# encoder_board.net
KiCad netlist of a schematic drawn in EAGLE
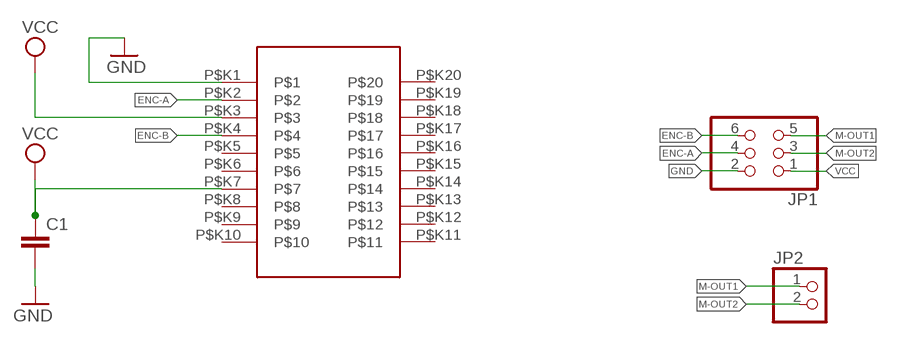
[diagram p0: schematic, sheet 1]

(export (version "E")
  (design (tool "Eeschema 10.0.6"))
  (components
    (comp (ref "C1")
      (value "C-EUC0805K")
      (footprint "eagle-import:C0805K")
      (libsource (lib "eagle-import") (part "C-EUC0805K"))
    )
    (comp (ref "JP1")
      (value "PINHD-2X3")
      (footprint "eagle-import:2X03")
      (libsource (lib "eagle-import") (part "PINHD-2X3"))
    )
    (comp (ref "JP2")
      (value "PINHD-1X2")
      (footprint "eagle-import:1X02")
      (libsource (lib "eagle-import") (part "PINHD-1X2"))
    )
    (comp (ref "U$1")
      (value "TSSOP20")
      (footprint "eagle-import:TSSOP20")
      (libsource (lib "eagle-import") (part "TSSOP20"))
    )
  )
  (nets
    (net (code "1") (name "ENC-A") (class "Default")
      (node (ref "JP1") (pin "4") (pinfunction "4_4") (pintype "passive"))
      (node (ref "U$1") (pin "P$K2") (pinfunction "P$2_P$K2") (pintype "bidirectional"))
    )
    (net (code "2") (name "ENC-B") (class "Default")
      (node (ref "JP1") (pin "6") (pinfunction "6_6") (pintype "passive"))
      (node (ref "U$1") (pin "P$K4") (pinfunction "P$4_P$K4") (pintype "bidirectional"))
    )
    (net (code "3") (name "GND") (class "Default")
      (node (ref "C1") (pin "2") (pinfunction "2_2") (pintype "passive"))
      (node (ref "JP1") (pin "2") (pinfunction "2_2") (pintype "passive"))
      (node (ref "U$1") (pin "P$K1") (pinfunction "P$1_P$K1") (pintype "bidirectional"))
    )
    (net (code "4") (name "M-OUT1") (class "Default")
      (node (ref "JP1") (pin "5") (pinfunction "5_5") (pintype "passive"))
      (node (ref "JP2") (pin "1") (pinfunction "1_1") (pintype "passive"))
    )
    (net (code "5") (name "M-OUT2") (class "Default")
      (node (ref "JP1") (pin "3") (pinfunction "3_3") (pintype "passive"))
      (node (ref "JP2") (pin "2") (pinfunction "2_2") (pintype "passive"))
    )
    (net (code "6") (name "VCC") (class "Default")
      (node (ref "C1") (pin "1") (pinfunction "1_1") (pintype "passive"))
      (node (ref "JP1") (pin "1") (pinfunction "1_1") (pintype "passive"))
      (node (ref "U$1") (pin "P$K3") (pinfunction "P$3_P$K3") (pintype "bidirectional"))
      (node (ref "U$1") (pin "P$K7") (pinfunction "P$7_P$K7") (pintype "bidirectional"))
    )
    (net (code "7") (name "unconnected-(U$1-P$5-PadP$K5)") (class "Default")
      (node (ref "U$1") (pin "P$K5") (pinfunction "P$5_P$K5") (pintype "bidirectional"))
    )
    (net (code "8") (name "unconnected-(U$1-P$6-PadP$K6)") (class "Default")
      (node (ref "U$1") (pin "P$K6") (pinfunction "P$6_P$K6") (pintype "bidirectional"))
    )
    (net (code "9") (name "unconnected-(U$1-P$8-PadP$K8)") (class "Default")
      (node (ref "U$1") (pin "P$K8") (pinfunction "P$8_P$K8") (pintype "bidirectional"))
    )
    (net (code "10") (name "unconnected-(U$1-P$9-PadP$K9)") (class "Default")
      (node (ref "U$1") (pin "P$K9") (pinfunction "P$9_P$K9") (pintype "bidirectional"))
    )
    (net (code "11") (name "unconnected-(U$1-P$10-PadP$K10)") (class "Default")
      (node (ref "U$1") (pin "P$K10") (pinfunction "P$10_P$K10") (pintype "bidirectional"))
    )
    (net (code "12") (name "unconnected-(U$1-P$11-PadP$K11)") (class "Default")
      (node (ref "U$1") (pin "P$K11") (pinfunction "P$11_P$K11") (pintype "bidirectional"))
    )
    (net (code "13") (name "unconnected-(U$1-P$12-PadP$K12)") (class "Default")
      (node (ref "U$1") (pin "P$K12") (pinfunction "P$12_P$K12") (pintype "bidirectional"))
    )
    (net (code "14") (name "unconnected-(U$1-P$13-PadP$K13)") (class "Default")
      (node (ref "U$1") (pin "P$K13") (pinfunction "P$13_P$K13") (pintype "bidirectional"))
    )
    (net (code "15") (name "unconnected-(U$1-P$14-PadP$K14)") (class "Default")
      (node (ref "U$1") (pin "P$K14") (pinfunction "P$14_P$K14") (pintype "bidirectional"))
    )
    (net (code "16") (name "unconnected-(U$1-P$15-PadP$K15)") (class "Default")
      (node (ref "U$1") (pin "P$K15") (pinfunction "P$15_P$K15") (pintype "bidirectional"))
    )
    (net (code "17") (name "unconnected-(U$1-P$16-PadP$K16)") (class "Default")
      (node (ref "U$1") (pin "P$K16") (pinfunction "P$16_P$K16") (pintype "bidirectional"))
    )
    (net (code "18") (name "unconnected-(U$1-P$17-PadP$K17)") (class "Default")
      (node (ref "U$1") (pin "P$K17") (pinfunction "P$17_P$K17") (pintype "bidirectional"))
    )
    (net (code "19") (name "unconnected-(U$1-P$18-PadP$K18)") (class "Default")
      (node (ref "U$1") (pin "P$K18") (pinfunction "P$18_P$K18") (pintype "bidirectional"))
    )
    (net (code "20") (name "unconnected-(U$1-P$19-PadP$K19)") (class "Default")
      (node (ref "U$1") (pin "P$K19") (pinfunction "P$19_P$K19") (pintype "bidirectional"))
    )
    (net (code "21") (name "unconnected-(U$1-P$20-PadP$K20)") (class "Default")
      (node (ref "U$1") (pin "P$K20") (pinfunction "P$20_P$K20") (pintype "bidirectional"))
    )
  )
)
